# WX0_010_982DL_1.net
KiCad netlist of a schematic drawn in Altium Designer
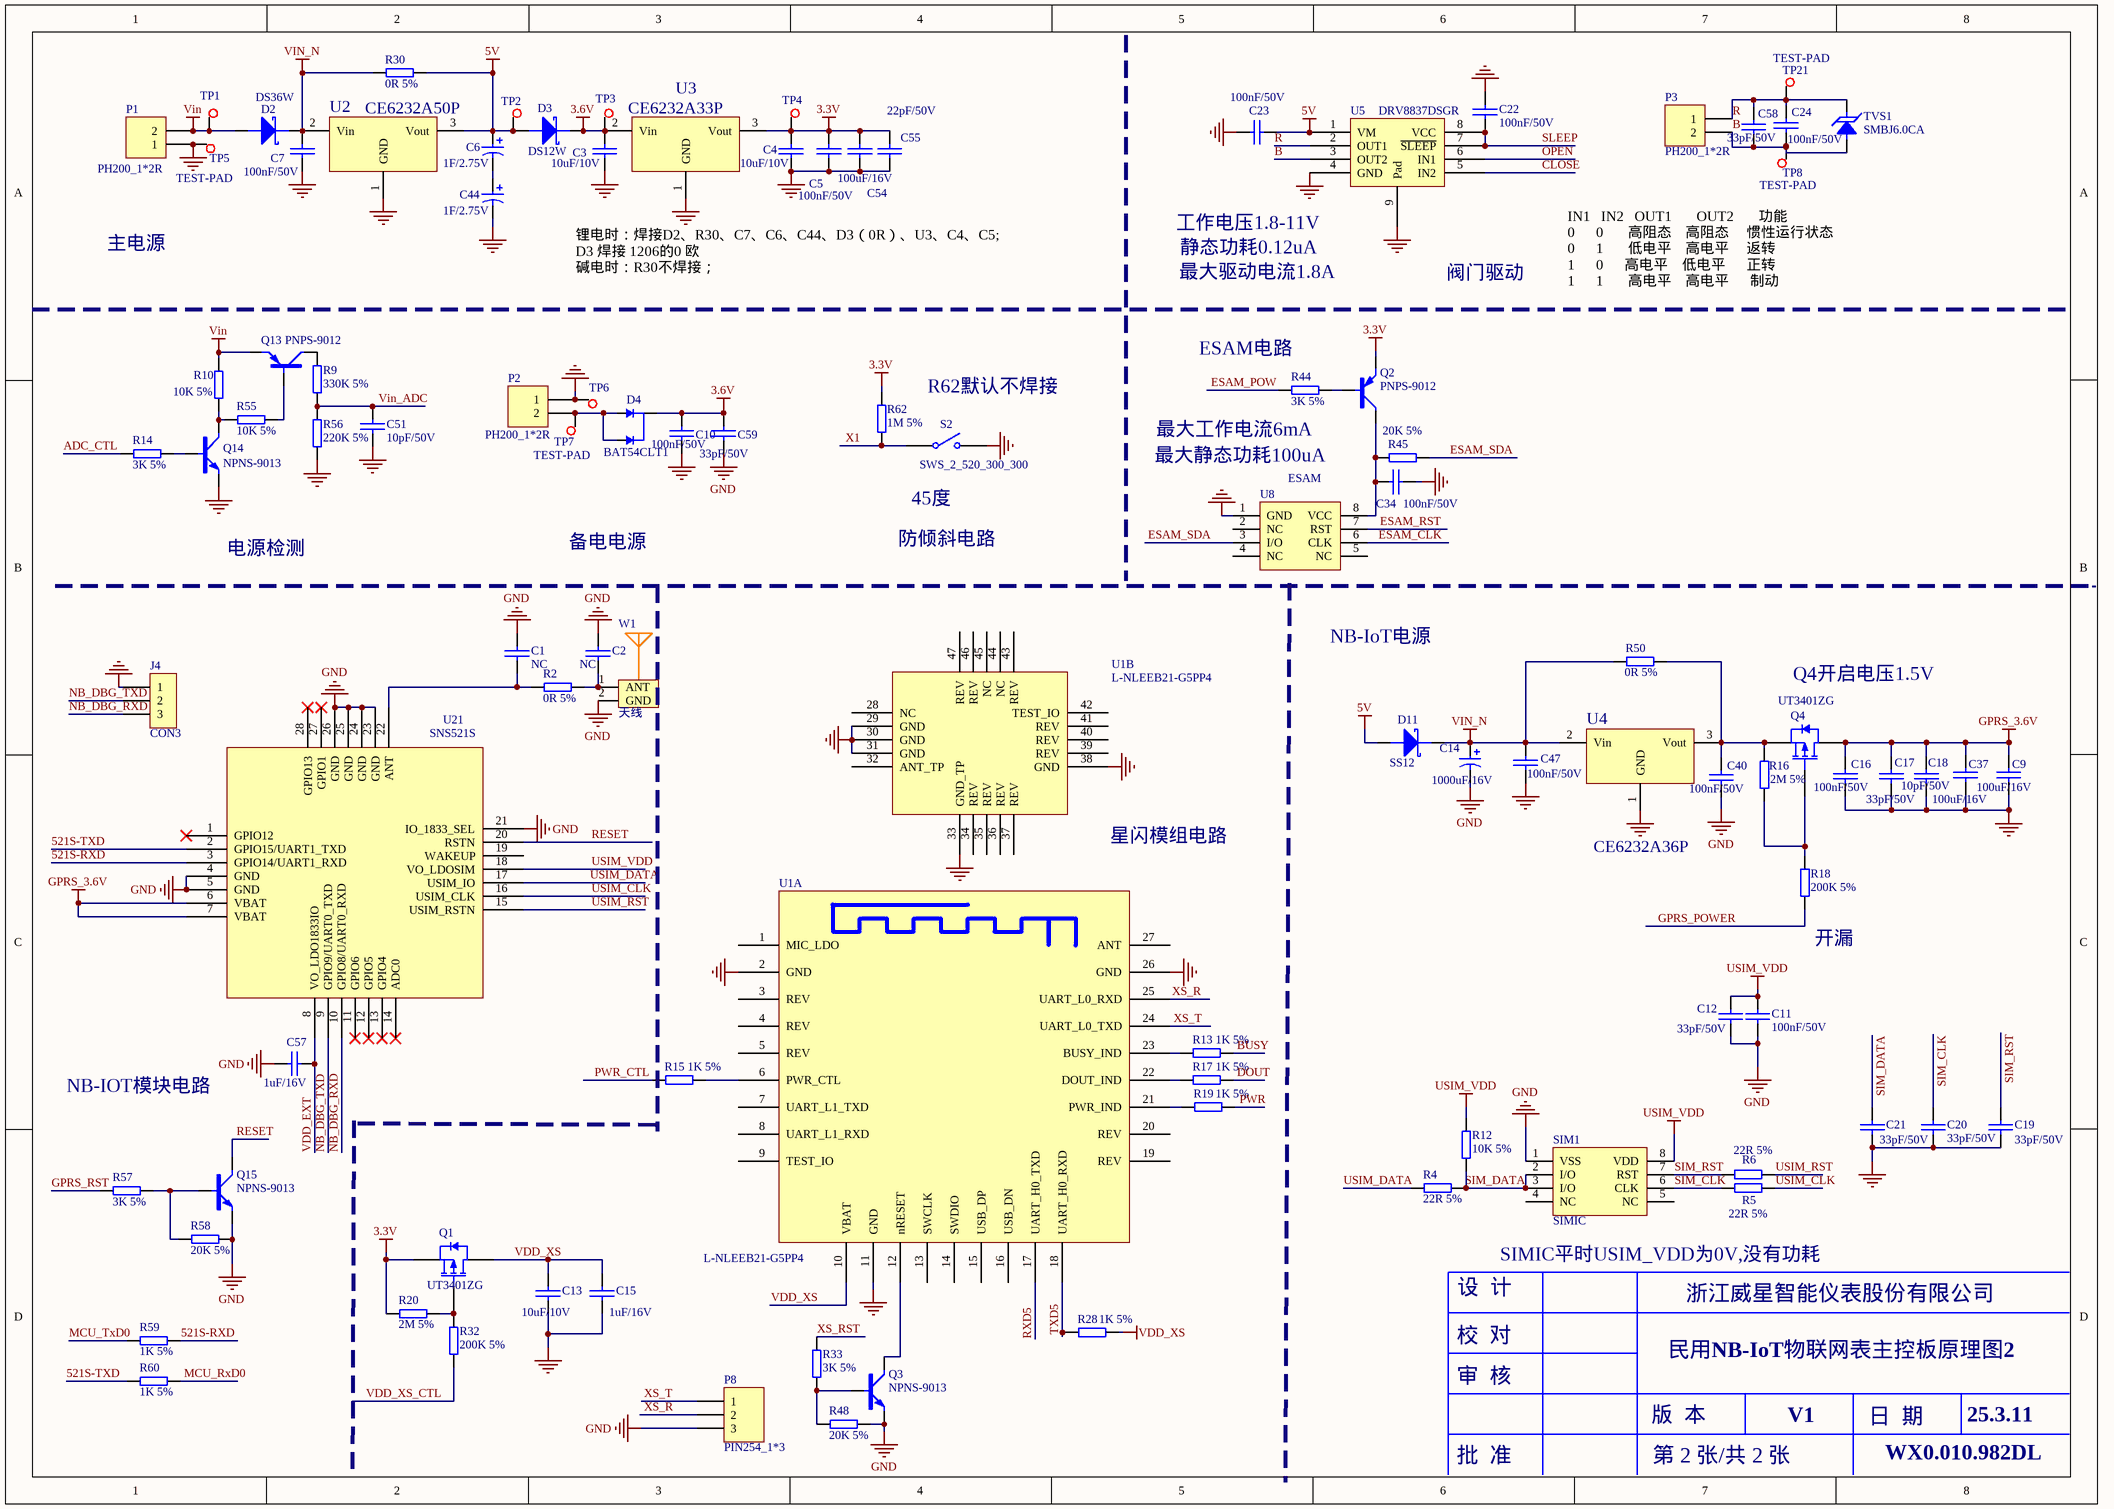
[diagram p0: WX0.010.982DL(1).SchDoc]

(export (version "E")
  (design (tool "Eeschema 10.0.6"))
  (components
    (comp (ref "C1")
      (value "NC")
      (footprint "CAP0603")
      (libsource (lib "Database_Libs2") (part "CC03JPO9_12P"))
    )
    (comp (ref "C2")
      (value "NC")
      (footprint "CAP0603")
      (libsource (lib "Database_Libs2") (part "CC03JPO9_12P"))
    )
    (comp (ref "C3")
      (value "10uF/10V")
      (footprint "CAP0603")
      (description "106pF,10 V,±10%,0603,村田,GRM188R61A106KE47D")
      (fields (field (name "PART NUMBER") "101020103-0026"))
      (libsource (lib "Database_Libs2") (part "CC03K5R6_10U"))
    )
    (comp (ref "C4")
      (value "10uF/10V")
      (footprint "CAP0603")
      (description "106pF,10 V,±10%,0603,村田,GRM188R61A106KE47D")
      (fields (field (name "PART NUMBER") "101020103-0026"))
      (libsource (lib "Database_Libs2") (part "CC03K5R6_10U"))
    )
    (comp (ref "C5")
      (value "100nF/50V")
      (footprint "CAP0603")
      (description "104pF,50 V,±10%,0603,国巨,CC0603KRX7R9BB104")
      (fields (field (name "PART NUMBER") "101020103-0021"))
      (libsource (lib "Database_Libs2") (part "CC03K7R9_100N"))
    )
    (comp (ref "C6")
      (value "1F/2.75V")
      (footprint "CAPPC_350_800_1600R")
      (description "1F,2.75 V,-20%~+20%,8mm*16mm,红宝石,2.7 DMC 1 M MY4 8X16")
      (fields (field (name "PART NUMBER") "1010202-0015"))
      (libsource (lib "Database_Libs2") (part "CALM3MRDMC_1F"))
    )
    (comp (ref "C7")
      (value "100nF/50V")
      (footprint "CAP0603")
      (description "104pF,50 V,±10%,0603,国巨,CC0603KRX7R9BB104")
      (fields (field (name "PART NUMBER") "101020103-0021"))
      (libsource (lib "Database_Libs2") (part "CC03K7R9_100N"))
    )
    (comp (ref "C9")
      (value "100uF/16V")
      (footprint "GRM31CR60J107ME39L")
      (libsource (lib "Database_Libs2") (part "CC06KPO7_106P"))
    )
    (comp (ref "C10")
      (value "100nF/50V")
      (footprint "CAP0603")
      (description "104pF,50 V,±10%,0603,国巨,CC0603KRX7R9BB104")
      (fields (field (name "PART NUMBER") "101020103-0021"))
      (libsource (lib "Database_Libs2") (part "CC03K7R9_100N"))
    )
    (comp (ref "C11")
      (value "100nF/50V")
      (footprint "CAP0603")
      (description "104pF,50 V,±10%,0603,国巨,CC0603KRX7R9BB104")
      (fields (field (name "PART NUMBER") "101020103-0021"))
      (libsource (lib "Database_Libs2") (part "CC03K7R9_100N"))
    )
    (comp (ref "C12")
      (value "33pF/50V")
      (footprint "CAP0603")
      (description "33pF,50 V,±10%,0603,国巨,CC0603KRNPO9BN33")
      (fields (field (name "PART NUMBER") "101020103-0027"))
      (libsource (lib "Database_Libs2") (part "CC03KPO9_33P"))
    )
    (comp (ref "C13")
      (value "10uF/10V")
      (footprint "CAP0603")
      (description "106pF,10 V,±10%,0603,村田,GRM188R61A106KE47D")
      (fields (field (name "PART NUMBER") "101020103-0026"))
      (libsource (lib "Database_Libs2") (part "CC03K5R6_10U"))
    )
    (comp (ref "C14")
      (value "1000uF/16V")
      (footprint "CAPPC_500_800_2000R")
      (description "1000UF,16V,±20%,贴片10*10.2MM,深圳市三炎科电子科技有限公司,16V1000UF")
      (fields (field (name "PART NUMBER") "1010203-0026"))
      (libsource (lib "Database_Libs2") (part "CAL7MRZLH_1000U_R"))
    )
    (comp (ref "C15")
      (value "1uF/16V")
      (footprint "CAP0603")
      (description "105pF,16 V,±10%,0603,国巨,CC0603KRX7R7BB105")
      (fields (field (name "PART NUMBER") "101020103-0003"))
      (libsource (lib "Database_Libs2") (part "CC03K7R7_1U"))
    )
    (comp (ref "C16")
      (value "100nF/50V")
      (footprint "CAP0603")
      (description "104pF,50 V,±10%,0603,国巨,CC0603KRX7R9BB104")
      (fields (field (name "PART NUMBER") "101020103-0021"))
      (libsource (lib "Database_Libs2") (part "CC03K7R9_100N"))
    )
    (comp (ref "C17")
      (value "33pF/50V")
      (footprint "CAP0603")
      (description "33pF,50 V,±10%,0603,国巨,CC0603KRNPO9BN33")
      (fields (field (name "PART NUMBER") "101020103-0027"))
      (libsource (lib "Database_Libs2") (part "CC03KPO9_33P"))
    )
    (comp (ref "C18")
      (value "10pF/50V")
      (footprint "CAP0603")
      (description "10pF,50 V,±5%,0603,X7R,国巨,CC0603JRNPO9BN100")
      (fields (field (name "PART NUMBER") "101020103-0014"))
      (libsource (lib "Database_Libs2") (part "CC03JPO9_10P"))
    )
    (comp (ref "C19")
      (value "33pF/50V")
      (footprint "CAP0603")
      (description "33pF,50 V,±10%,0603,国巨,CC0603KRNPO9BN33")
      (fields (field (name "PART NUMBER") "101020103-0027"))
      (libsource (lib "Database_Libs2") (part "CC03KPO9_33P"))
    )
    (comp (ref "C20")
      (value "33pF/50V")
      (footprint "CAP0603")
      (description "33pF,50 V,±10%,0603,国巨,CC0603KRNPO9BN33")
      (fields (field (name "PART NUMBER") "101020103-0027"))
      (libsource (lib "Database_Libs2") (part "CC03KPO9_33P"))
    )
    (comp (ref "C21")
      (value "33pF/50V")
      (footprint "CAP0603")
      (description "33pF,50 V,±10%,0603,国巨,CC0603KRNPO9BN33")
      (fields (field (name "PART NUMBER") "101020103-0027"))
      (libsource (lib "Database_Libs2") (part "CC03KPO9_33P"))
    )
    (comp (ref "C22")
      (value "100nF/50V")
      (footprint "CAP0603")
      (description "104pF,50 V,±10%,0603,国巨,CC0603KRX7R9BB104")
      (fields (field (name "PART NUMBER") "101020103-0021"))
      (libsource (lib "Database_Libs2") (part "CC03K7R9_100N"))
    )
    (comp (ref "C23")
      (value "100nF/50V")
      (footprint "CAP0603")
      (description "104pF,50 V,±10%,0603,国巨,CC0603KRX7R9BB104")
      (fields (field (name "PART NUMBER") "101020103-0021"))
      (libsource (lib "Database_Libs2") (part "CC03K7R9_100N"))
    )
    (comp (ref "C24")
      (value "100nF/50V")
      (footprint "CAP0603")
      (description "104pF,50 V,±10%,0603,国巨,CC0603KRX7R9BB104")
      (fields (field (name "PART NUMBER") "101020103-0021"))
      (libsource (lib "Database_Libs2") (part "CC03K7R9_100N"))
    )
    (comp (ref "C34")
      (value "100nF/50V")
      (footprint "CAP0603")
      (description "104pF,50 V,±10%,0603,国巨,CC0603KRX7R9BB104")
      (fields (field (name "PART NUMBER") "101020103-0021"))
      (libsource (lib "Database_Libs2") (part "CC03K7R9_100N"))
    )
    (comp (ref "C37")
      (value "100uF/16V")
      (footprint "GRM31CR60J107ME39L")
      (libsource (lib "Database_Libs2") (part "CC06KPO7_106P"))
    )
    (comp (ref "C40")
      (value "100nF/50V")
      (footprint "CAP0603")
      (description "104pF,50 V,±10%,0603,国巨,CC0603KRX7R9BB104")
      (fields (field (name "PART NUMBER") "101020103-0021"))
      (libsource (lib "Database_Libs2") (part "CC03K7R9_100N"))
    )
    (comp (ref "C44")
      (value "1F/2.75V")
      (footprint "CAPPC_350_800_1600R")
      (description "1F,2.75 V,-20%~+20%,8mm*16mm,红宝石,2.7 DMC 1 M MY4 8X16")
      (fields (field (name "PART NUMBER") "1010202-0015"))
      (libsource (lib "Database_Libs2") (part "CALM3MRDMC_1F"))
    )
    (comp (ref "C47")
      (value "100nF/50V")
      (footprint "CAP0603")
      (description "104pF,50 V,±10%,0603,国巨,CC0603KRX7R9BB104")
      (fields (field (name "PART NUMBER") "101020103-0021"))
      (libsource (lib "Database_Libs2") (part "CC03K7R9_100N"))
    )
    (comp (ref "C51")
      (value "10pF/50V")
      (footprint "CAP0603")
      (description "10pF,50 V,±5%,0603,X7R,国巨,CC0603JRNPO9BN100")
      (fields (field (name "PART NUMBER") "101020103-0014"))
      (libsource (lib "Database_Libs2") (part "CC03JPO9_10P"))
    )
    (comp (ref "C54")
      (value "100uF/16V")
      (footprint "GRM31CR60J107ME39L")
      (description "100u,16 V,±10%,1206,国巨,CC1206KRNPO7BN106P")
      (libsource (lib "Database_Libs2") (part "CC06KPO7_106P"))
    )
    (comp (ref "C55")
      (value "22pF/50V")
      (footprint "CAP0603")
      (description "22pF,50 V,±5%,0603,国巨,CC0603JRNPO9BN22")
      (fields (field (name "PART NUMBER") "101020103-0009"))
      (libsource (lib "Database_Libs2") (part "CC03JPO9_22P"))
    )
    (comp (ref "C57")
      (value "1uF/16V")
      (footprint "CAP0603")
      (description "105pF,16 V,±10%,0603,国巨,CC0603KRX7R7BB105")
      (fields (field (name "PART NUMBER") "101020103-0003"))
      (libsource (lib "Database_Libs1") (part "CC03K7R7_1U"))
    )
    (comp (ref "C58")
      (value "33pF/50V")
      (footprint "CAP0603")
      (description "104pF,50 V,±10%,0603,国巨,CC0603KRX7R9BB104")
      (fields (field (name "PART NUMBER") "101020103-0021"))
      (libsource (lib "Database_Libs2") (part "CC03K7R9_100N"))
    )
    (comp (ref "C59")
      (value "33pF/50V")
      (footprint "CAP0603")
      (description "104pF,50 V,±10%,0603,国巨,CC0603KRX7R9BB104")
      (fields (field (name "PART NUMBER") "101020103-0021"))
      (libsource (lib "Database_Libs2") (part "CC03K7R9_100N"))
    )
    (comp (ref "D2")
      (value "DS36W")
      (footprint "SOD-123FL")
      (description "DS36W,SOD123-FL,3 A,42 V,60 V,浙江领晨科技有限公司,DS36W")
      (fields (field (name "PART NUMBER") "101040101-0055"))
      (libsource (lib "Database_Libs2") (part "02_DS12W"))
    )
    (comp (ref "D3")
      (value "DS12W")
      (footprint "SOD-123FL")
      (description "DS12W,SOD-123FL,1 A,0.55 V,20 V,领晨科技,DS12W")
      (fields (field (name "PART NUMBER") "101040101-0048"))
      (libsource (lib "Database_Libs2") (part "02_DS12W"))
    )
    (comp (ref "D4")
      (value "BAT54CLT1")
      (footprint "SOT-23")
      (description "BAT54CLT1，SOT23-3,SOT23-3,0.2 A,0.8 V,30 V,安森美,BAT54CLT1")
      (fields (field (name "PART NUMBER") "101040101-0038"))
      (libsource (lib "Database_Libs2") (part "02_BAT54CLT1"))
    )
    (comp (ref "D11")
      (value "SS12")
      (footprint "DO-214AC")
      (description "SS12,DO-214AC,1 A,0.55 V,20 V,昶鑫,SS12")
      (fields (field (name "PART NUMBER") "101040101-0009"))
      (libsource (lib "Database_Libs2") (part "02_SS12"))
    )
    (comp (ref "J4")
      (value "CON3")
      (footprint "PIN254_1*3*WXHJ")
      (description "Connector")
      (libsource (lib "Miscellaneous Devices") (part "CON3"))
    )
    (comp (ref "P1")
      (value "PH200_1*2R")
      (description "2.0-2AW,直插弯座，2PIN，脚间距2mm，带防翘起,公头,单排,2.0-2AW;直插弯座，2PIN,脚间距2mm，带防翘起")
      (fields (field (name "PART NUMBER") "1010902-0105"))
      (libsource (lib "") (part "PH200_1*2R_1"))
    )
    (comp (ref "P2")
      (value "PH200_1*2R")
      (description "2.0-2AW,直插弯座，2PIN，脚间距2mm，带防翘起,公头,单排,2.0-2AW;直插弯座，2PIN,脚间距2mm，带防翘起")
      (fields (field (name "PART NUMBER") "1010902-0105"))
      (libsource (lib "Database_Libs2") (part "PH200_1*2R"))
    )
    (comp (ref "P3")
      (value "PH200_1*2R")
      (footprint "PH200_1*2R")
      (description "2.0-2AW,直插弯座，2PIN，脚间距2mm，带防翘起,公头,单排,2.0-2AW;直插弯座，2PIN,脚间距2mm，带防翘起")
      (fields (field (name "PART NUMBER") "1010902-0105"))
      (libsource (lib "Database_Libs2") (part "PH200_1*2R"))
    )
    (comp (ref "P8")
      (value "PIN254_1*3")
      (footprint "PIN254_1*3*WXHJ")
      (libsource (lib "Connect_WX") (part "PIN254_1*3"))
    )
    (comp (ref "Q1")
      (value "UT3401ZG")
      (footprint "SOT-23")
      (description "UT3401ZG,P-MOS,SOT-23,UTC,UT3401ZG")
      (fields (field (name "PART NUMBER") "101040201-0013"))
      (libsource (lib "Database_Libs2") (part "03_P-UT3401ZG"))
    )
    (comp (ref "Q2")
      (value "PNPS-9012")
      (footprint "SOT-23")
      (description "9012,PNP,SOT-23,JCET;长电,S9012")
      (fields (field (name "PART NUMBER") "101040201-0001"))
      (libsource (lib "Database_Libs2") (part "03_PNPS-9012"))
    )
    (comp (ref "Q3")
      (value "NPNS-9013")
      (footprint "SOT-23")
      (description "9013,NPN,SOT-23,长电,S9013")
      (fields (field (name "PART NUMBER") "101040201-0002"))
      (libsource (lib "Database_Libs2") (part "03_NPNS-9013"))
    )
    (comp (ref "Q4")
      (value "UT3401ZG")
      (footprint "SOT-23")
      (description "UT3401ZG,P-MOS,SOT-23,UTC,UT3401ZG")
      (fields (field (name "PART NUMBER") "101040201-0013"))
      (libsource (lib "Database_Libs2") (part "03_P-UT3401ZG"))
    )
    (comp (ref "Q13")
      (value "PNPS-9012")
      (footprint "SOT-23")
      (description "9012,PNP,SOT-23,JCET;长电,S9012")
      (fields (field (name "PART NUMBER") "101040201-0001"))
      (libsource (lib "Database_Libs2") (part "03_PNPS-9012"))
    )
    (comp (ref "Q14")
      (value "NPNS-9013")
      (footprint "SOT-23")
      (description "9013,NPN,SOT-23,长电,S9013")
      (fields (field (name "PART NUMBER") "101040201-0002"))
      (libsource (lib "Database_Libs2") (part "03_NPNS-9013"))
    )
    (comp (ref "Q15")
      (value "NPNS-9013")
      (footprint "SOT-23")
      (description "9013,NPN,SOT-23,长电,S9013")
      (fields (field (name "PART NUMBER") "101040201-0002"))
      (libsource (lib "Database_Libs2") (part "03_NPNS-9013"))
    )
    (comp (ref "R2")
      (value "0R 5%")
      (footprint "RES0603")
      (description "国巨,±5%,0603,,155 ℃,-55 ℃,RC0603J2-070RL,无铅,200 ppm/℃,1/10W,,0R")
      (fields (field (name "PART NUMBER") "101010103-0001"))
      (libsource (lib "Database_Libs2") (part "RC03J_0R"))
    )
    (comp (ref "R4")
      (value "22R 5%")
      (footprint "RES0603")
      (description "国巨,±5%,0603,,155 ℃,-55 ℃,RC0603JR-0722RL,无铅,200 ppm/℃,1/10W,,22欧")
      (fields (field (name "PART NUMBER") "101010103-0009"))
      (libsource (lib "Database_Libs2") (part "RC03J_22R"))
    )
    (comp (ref "R5")
      (value "22R 5%")
      (footprint "RES0603")
      (description "国巨,±5%,0603,,155 ℃,-55 ℃,RC0603JR-0722RL,无铅,200 ppm/℃,1/10W,,22欧")
      (fields (field (name "PART NUMBER") "101010103-0009"))
      (libsource (lib "Database_Libs2") (part "RC03J_22R"))
    )
    (comp (ref "R6")
      (value "22R 5%")
      (footprint "RES0603")
      (description "国巨,±5%,0603,,155 ℃,-55 ℃,RC0603JR-0722RL,无铅,200 ppm/℃,1/10W,,22欧")
      (fields (field (name "PART NUMBER") "101010103-0009"))
      (libsource (lib "Database_Libs2") (part "RC03J_22R"))
    )
    (comp (ref "R9")
      (value "330K 5%")
      (footprint "RES0603")
      (description "330K,±5%,1/10W,0603,国巨,RC0603JR-07330KL")
      (fields (field (name "PART NUMBER") "101010103-0066"))
      (libsource (lib "Database_Libs2") (part "RC03J_330K"))
    )
    (comp (ref "R10")
      (value "10K 5%")
      (footprint "RES0603")
      (description "国巨,±5%,0603,,155 ℃,-55 ℃,RC0603JR-0710KL,无铅,200 ppm/℃,1/10W,,10K")
      (fields (field (name "PART NUMBER") "101010103-0003"))
      (libsource (lib "Database_Libs2") (part "RC03J_10K"))
    )
    (comp (ref "R12")
      (value "10K 5%")
      (footprint "RES0603")
      (description "国巨,±5%,0603,,155 ℃,-55 ℃,RC0603JR-0722RL,无铅,200 ppm/℃,1/10W,,22欧")
      (fields (field (name "PART NUMBER") "101010103-0009"))
      (libsource (lib "Database_Libs2") (part "RC03J_22R"))
    )
    (comp (ref "R13")
      (value "1K 5%")
      (footprint "RES0603")
      (description "1K,±5%,1/10W,0603,国巨,RC0603JR-071KL")
      (fields (field (name "PART NUMBER") "101010103-0008"))
      (libsource (lib "Database_Libs2") (part "RC03J_1K"))
    )
    (comp (ref "R14")
      (value "3K 5%")
      (footprint "RES0603")
      (description "国巨,±5%,0603,,155 ℃,-55 ℃,RC0603JR-073KL,无铅,100 ppm/℃,1/10W,,3K")
      (fields (field (name "PART NUMBER") "101010103-0006"))
      (libsource (lib "Database_Libs2") (part "RC03J_3K"))
    )
    (comp (ref "R15")
      (value "1K 5%")
      (footprint "RES0603")
      (description "1K,±5%,1/10W,0603,国巨,RC0603JR-071KL")
      (fields (field (name "PART NUMBER") "101010103-0008"))
      (libsource (lib "Database_Libs2") (part "RC03J_1K"))
    )
    (comp (ref "R16")
      (value "2M 5%")
      (footprint "RES0603")
      (description "国巨,±5%,0603,,155 ℃,-55 ℃,RC0603JR-072ML,含铅,100 ppm/℃,1/10W,,2M")
      (fields (field (name "PART NUMBER") "101010103-0025"))
      (libsource (lib "Database_Libs2") (part "RC03J_2M"))
    )
    (comp (ref "R17")
      (value "1K 5%")
      (footprint "RES0603")
      (description "1K,±5%,1/10W,0603,国巨,RC0603JR-071KL")
      (fields (field (name "PART NUMBER") "101010103-0008"))
      (libsource (lib "Database_Libs2") (part "RC03J_1K"))
    )
    (comp (ref "R18")
      (value "200K 5%")
      (footprint "RES0603")
      (description "200K,±5%,1/10W,0603,国巨,RC0603JR-07200KL")
      (fields (field (name "PART NUMBER") "101010103-0034"))
      (libsource (lib "Database_Libs2") (part "RC03J_200K"))
    )
    (comp (ref "R19")
      (value "1K 5%")
      (footprint "RES0603")
      (description "1K,±5%,1/10W,0603,国巨,RC0603JR-071KL")
      (fields (field (name "PART NUMBER") "101010103-0008"))
      (libsource (lib "Database_Libs2") (part "RC03J_1K"))
    )
    (comp (ref "R20")
      (value "2M 5%")
      (footprint "RES0603")
      (description "10K±5%,1/10W,0603")
      (fields (field (name "PART NUMBER") "101010103-0003"))
      (libsource (lib "Database_Libs1") (part "RC03JF_10K"))
    )
    (comp (ref "R28")
      (value "1K 5%")
      (footprint "RES0603")
      (description "1K,±5%,1/10W,0603,国巨,RC0603JR-071KL")
      (fields (field (name "PART NUMBER") "101010103-0008"))
      (libsource (lib "Database_Libs2") (part "RC03J_1K"))
    )
    (comp (ref "R30")
      (value "0R 5%")
      (footprint "RES1206")
      (description "0Ω,±5%,1/4W,1206,国巨,RC1206JR-070RL")
      (fields (field (name "PART NUMBER") "101010101-0013"))
      (libsource (lib "Database_Libs2") (part "RC06J_0R"))
    )
    (comp (ref "R32")
      (value "200K 5%")
      (footprint "RES0603")
      (description "10K±5%,1/10W,0603")
      (fields (field (name "PART NUMBER") "101010103-0003"))
      (libsource (lib "Database_Libs1") (part "RC03JF_10K"))
    )
    (comp (ref "R33")
      (value "3K 5%")
      (footprint "RES0603")
      (description "国巨,±5%,0603,,155 ℃,-55 ℃,RC0603JR-073KL,无铅,100 ppm/℃,1/10W,,3K")
      (fields (field (name "PART NUMBER") "101010103-0006"))
      (libsource (lib "Database_Libs2") (part "RC03J_3K"))
    )
    (comp (ref "R44")
      (value "3K 5%")
      (footprint "RES0603")
      (description "国巨,±5%,0603,,155 ℃,-55 ℃,RC0603JR-0710KL,无铅,200 ppm/℃,1/10W,,10K")
      (fields (field (name "PART NUMBER") "101010103-0003"))
      (libsource (lib "Database_Libs2") (part "RC03J_10K"))
    )
    (comp (ref "R45")
      (value "20K 5%")
      (footprint "RES0603")
      (description "国巨,±5%,0603,,155 ℃,-55 ℃,RC0603JR-0720KL,无铅,200 ppm/℃,1/10W,,20K")
      (fields (field (name "PART NUMBER") "101010103-0004"))
      (libsource (lib "Database_Libs2") (part "RC03J_20K"))
    )
    (comp (ref "R48")
      (value "20K 5%")
      (footprint "RES0603")
      (description "国巨,±5%,0603,,155 ℃,-55 ℃,RC0603JR-0720KL,无铅,200 ppm/℃,1/10W,,20K")
      (fields (field (name "PART NUMBER") "101010103-0004"))
      (libsource (lib "Database_Libs2") (part "RC03J_20K"))
    )
    (comp (ref "R50")
      (value "0R 5%")
      (footprint "RES1206")
      (description "0Ω,±5%,1/4W,1206,国巨,RC1206JR-070RL")
      (fields (field (name "PART NUMBER") "101010101-0013"))
      (libsource (lib "Database_Libs2") (part "RC06J_0R"))
    )
    (comp (ref "R55")
      (value "10K 5%")
      (footprint "RES0603")
      (description "国巨,±5%,0603,,155 ℃,-55 ℃,RC0603JR-0710KL,无铅,200 ppm/℃,1/10W,,10K")
      (fields (field (name "PART NUMBER") "101010103-0003"))
      (libsource (lib "Database_Libs2") (part "RC03J_10K"))
    )
    (comp (ref "R56")
      (value "220K 5%")
      (footprint "RES0603")
      (description "220K,±5%,1/10W,0603,国巨,RC0603JR-07220KL")
      (fields (field (name "PART NUMBER") "101010103-0044"))
      (libsource (lib "Database_Libs2") (part "RC03J_220K"))
    )
    (comp (ref "R57")
      (value "3K 5%")
      (footprint "RES0603")
      (description "国巨,±5%,0603,,155 ℃,-55 ℃,RC0603JR-073KL,无铅,100 ppm/℃,1/10W,,3K")
      (fields (field (name "PART NUMBER") "101010103-0006"))
      (libsource (lib "Database_Libs2") (part "RC03J_3K"))
    )
    (comp (ref "R58")
      (value "20K 5%")
      (footprint "RES0603")
      (description "国巨,±5%,0603,,155 ℃,-55 ℃,RC0603JR-0720KL,无铅,200 ppm/℃,1/10W,,20K")
      (fields (field (name "PART NUMBER") "101010103-0004"))
      (libsource (lib "Database_Libs2") (part "RC03J_20K"))
    )
    (comp (ref "R59")
      (value "1K 5%")
      (footprint "RES0603")
      (description "4.7K±5%,1/10W,0603")
      (fields (field (name "PART NUMBER") "101010103-0042"))
      (libsource (lib "Database_Libs2") (part "RC03J_4.7K"))
    )
    (comp (ref "R60")
      (value "1K 5%")
      (footprint "RES0603")
      (description "1K,±5%,1/10W,0603,国巨,RC0603JR-071KL")
      (fields (field (name "PART NUMBER") "101010103-0008"))
      (libsource (lib "Database_Libs2") (part "RC03J_1K"))
    )
    (comp (ref "R62")
      (value "1M 5%")
      (footprint "RES0603")
      (description "国巨,±5%,0603,,155 ℃,-55 ℃,RC0603JR-071ML,无铅,200 ppm/℃,1/10W,,1M")
      (fields (field (name "PART NUMBER") "101010103-0002"))
      (libsource (lib "Database_Libs2") (part "RC03J_1M"))
    )
    (comp (ref "S2")
      (value "SWS_2_520_300_300")
      (footprint "SWS_2_520_300")
      (description "CSX-SEN-645B,垂直45°开关转换,3*5.2mm,360°任意方位倾斜检测,深圳市成晟科技有限公司")
      (fields (field (name "PART NUMBER") "1011001-0051"))
      (libsource (lib "Database_Libs2") (part "07_SWS_2_520_300_300"))
    )
    (comp (ref "SIM1")
      (value "SIMIC")
      (footprint "SIMIC")
      (description "SIMIC虚拟器件")
      (fields (field (name "PART NUMBER") "AD_XN_SIMIC_01"))
      (libsource (lib "Database_Libs2") (part "05_SIMIC"))
    )
    (comp (ref "TP1")
      (value "TEST-PAD")
      (footprint "TEST-PAD")
      (description "单面焊盘测试点")
      (fields (field (name "PART NUMBER") "AD_WXHJ_TEST-PAD_01"))
      (libsource (lib "Database_Libs2") (part "TEST-PAD"))
    )
    (comp (ref "TP2")
      (value "TEST-PAD")
      (footprint "TEST-PAD")
      (description "单面焊盘测试点")
      (fields (field (name "PART NUMBER") "AD_WXHJ_TEST-PAD_01"))
      (libsource (lib "Database_Libs2") (part "TEST-PAD"))
    )
    (comp (ref "TP3")
      (value "TEST-PAD")
      (footprint "TEST-PAD")
      (description "单面焊盘测试点")
      (fields (field (name "PART NUMBER") "AD_WXHJ_TEST-PAD_01"))
      (libsource (lib "Database_Libs2") (part "TEST-PAD"))
    )
    (comp (ref "TP4")
      (value "TEST-PAD")
      (footprint "TEST-PAD")
      (description "单面焊盘测试点")
      (fields (field (name "PART NUMBER") "AD_WXHJ_TEST-PAD_01"))
      (libsource (lib "Database_Libs2") (part "TEST-PAD"))
    )
    (comp (ref "TP5")
      (value "TEST-PAD")
      (footprint "TEST-PAD")
      (description "单面焊盘测试点")
      (fields (field (name "PART NUMBER") "AD_WXHJ_TEST-PAD_01"))
      (libsource (lib "Database_Libs2") (part "TEST-PAD"))
    )
    (comp (ref "TP6")
      (value "TEST-PAD")
      (footprint "TEST-PAD")
      (description "单面焊盘测试点")
      (fields (field (name "PART NUMBER") "AD_WXHJ_TEST-PAD_01"))
      (libsource (lib "Database_Libs2") (part "TEST-PAD"))
    )
    (comp (ref "TP7")
      (value "TEST-PAD")
      (footprint "TEST-PAD")
      (description "单面焊盘测试点")
      (fields (field (name "PART NUMBER") "AD_WXHJ_TEST-PAD_01"))
      (libsource (lib "Database_Libs2") (part "TEST-PAD"))
    )
    (comp (ref "TP8")
      (value "TEST-PAD")
      (footprint "TEST-PAD")
      (description "单面焊盘测试点")
      (fields (field (name "PART NUMBER") "AD_WXHJ_TEST-PAD_01"))
      (libsource (lib "Database_Libs2") (part "TEST-PAD"))
    )
    (comp (ref "TP21")
      (value "TEST-PAD")
      (footprint "TEST-PAD")
      (description "单面焊盘测试点")
      (fields (field (name "PART NUMBER") "AD_WXHJ_TEST-PAD_01"))
      (libsource (lib "Database_Libs2") (part "TEST-PAD"))
    )
    (comp (ref "TVS1")
      (value "SMBJ6.0CA")
      (footprint "DO-214AA")
      (description "SMBJ6.0CA,DO-214AA,10.3 V,6.0 V,600 W,58.3 A,800 uA,上海君耀电子有限公司,SMBJ6.0CA")
      (fields (field (name "PART NUMBER") "101040101-0024"))
      (libsource (lib "Database_Libs2") (part "05_SMBJ6.0CA"))
    )
    (comp (ref "U1")
      (value "L-NLEEB21-G5PP4")
      (footprint "L-NLEEB21-G5BP4")
      (libsource (lib "L-NLEEB21-G5BP4_V03") (part "L-NLEEB21-G5BP4"))
    )
    (comp (ref "U2")
      (value "CE6232A50P")
      (footprint "SOT-89")
      (fields (field (name "PART NUMBER") "1010503-0013"))
      (libsource (lib "Database_Libs2") (part "02_S-1206B50-U3"))
    )
    (comp (ref "U3")
      (value "CE6232A33P")
      (footprint "SOT-89")
      (fields (field (name "PART NUMBER") "1010503-0002"))
      (libsource (lib "Database_Libs2") (part "02_S-1206B33-U3T1G"))
    )
    (comp (ref "U4")
      (value "CE6232A36P")
      (footprint "SOT-89")
      (description "CE6232A36P,CE6232A36P,SOT89-3,8 V,1.8 V,0.11 V,3.6 V,600mA,0.8 uA,南京芯力微电子有限公司")
      (fields (field (name "PART NUMBER") "1010503-0031"))
      (libsource (lib "Database_Libs2") (part "02_CE6232A36P"))
    )
    (comp (ref "U5")
      (value "DRV8837DSGR")
      (footprint "S-PWSON-N8")
      (description "DRV8837DSGR,S-PWSON-N8,TI,DRV8837DSGR")
      (fields (field (name "PART NUMBER") "101050101-0060"))
      (libsource (lib "Database_Libs2") (part "07_DRV8837DSGR"))
    )
    (comp (ref "U8")
      (value "ESAM")
      (footprint "SOP-8")
      (description "ESAM虚拟器件")
      (fields (field (name "PART NUMBER") "AD_XN_ESAM_01"))
      (libsource (lib "Database_Libs2") (part "04_ESAM"))
    )
    (comp (ref "U21") (value "SNS521S") (libsource (lib "Schlib1") (part "OUT")))
    (comp (ref "W1")
      (value "天线")
      (footprint "ANT-IPEX_1")
      (description "UB06000058A,3*3.1*1.25mm,公头,单排,IPEX一代板端")
      (fields (field (name "PART NUMBER") "1010902-0145"))
      (libsource (lib "Database_Libs2") (part "天线"))
    )
  )
  (nets
    (net (code "1") (name "/521S-RXD") (class "Default")
      (node (ref "R59") (pin "1") (pinfunction "1_1") (pintype "passive"))
      (node (ref "U21") (pin "3") (pinfunction "GPIO14/UART1_RXD_3") (pintype "passive"))
    )
    (net (code "2") (name "/521S-TXD") (class "Default")
      (node (ref "R60") (pin "2") (pinfunction "2_2") (pintype "passive"))
      (node (ref "U21") (pin "2") (pinfunction "GPIO15/UART1_TXD_2") (pintype "passive"))
    )
    (net (code "3") (name "/ADC_CTL") (class "Default")
      (node (ref "R14") (pin "1") (pinfunction "1_1") (pintype "passive"))
    )
    (net (code "4") (name "/B") (class "Default")
      (node (ref "C24") (pin "2") (pinfunction "2_2") (pintype "passive"))
      (node (ref "C58") (pin "2") (pinfunction "2_2") (pintype "passive"))
      (node (ref "P3") (pin "2") (pinfunction "2_2") (pintype "passive"))
      (node (ref "TP8") (pin "1") (pinfunction "1_1") (pintype "passive"))
      (node (ref "TVS1") (pin "1") (pinfunction "1_1") (pintype "passive"))
      (node (ref "U5") (pin "3") (pinfunction "OUT2_3") (pintype "passive"))
    )
    (net (code "5") (name "/BUSY") (class "Default")
      (node (ref "R13") (pin "1") (pinfunction "1_1") (pintype "passive"))
    )
    (net (code "6") (name "/CLOSE") (class "Default")
      (node (ref "U5") (pin "5") (pinfunction "IN2_5") (pintype "passive"))
    )
    (net (code "7") (name "/DOUT") (class "Default")
      (node (ref "R17") (pin "1") (pinfunction "1_1") (pintype "passive"))
    )
    (net (code "8") (name "/ESAM_CLK") (class "Default")
      (node (ref "U8") (pin "6") (pinfunction "CLK_6") (pintype "passive"))
    )
    (net (code "9") (name "/ESAM_POW") (class "Default")
      (node (ref "R44") (pin "1") (pinfunction "1_1") (pintype "passive"))
    )
    (net (code "10") (name "/ESAM_RST") (class "Default")
      (node (ref "U8") (pin "7") (pinfunction "RST_7") (pintype "passive"))
    )
    (net (code "11") (name "/ESAM_SDA") (class "Default")
      (node (ref "R45") (pin "2") (pinfunction "2_2") (pintype "passive"))
      (node (ref "U8") (pin "3") (pinfunction "I/O_3") (pintype "passive"))
    )
    (net (code "12") (name "/GPRS_POWER") (class "Default")
      (node (ref "R18") (pin "1") (pinfunction "1_1") (pintype "passive"))
    )
    (net (code "13") (name "/GPRS_RST") (class "Default")
      (node (ref "R57") (pin "1") (pinfunction "1_1") (pintype "passive"))
    )
    (net (code "14") (name "/MCU_RxD0") (class "Default")
      (node (ref "R60") (pin "1") (pinfunction "1_1") (pintype "passive"))
    )
    (net (code "15") (name "/MCU_TxD0") (class "Default")
      (node (ref "R59") (pin "2") (pinfunction "2_2") (pintype "passive"))
    )
    (net (code "16") (name "/NB_DBG_RXD") (class "Default")
      (node (ref "J4") (pin "3") (pinfunction "3_3") (pintype "passive"))
      (node (ref "U21") (pin "10") (pinfunction "GPIO8/UART0_RXD_10") (pintype "passive"))
    )
    (net (code "17") (name "/NB_DBG_TXD") (class "Default")
      (node (ref "J4") (pin "2") (pinfunction "2_2") (pintype "passive"))
      (node (ref "U21") (pin "9") (pinfunction "GPIO9/UART0_TXD_9") (pintype "passive"))
    )
    (net (code "18") (name "/OPEN") (class "Default")
      (node (ref "U5") (pin "6") (pinfunction "IN1_6") (pintype "passive"))
    )
    (net (code "19") (name "/PWR") (class "Default")
      (node (ref "R19") (pin "1") (pinfunction "1_1") (pintype "passive"))
    )
    (net (code "20") (name "/PWR_CTL") (class "Default")
      (node (ref "R15") (pin "2") (pinfunction "2_2") (pintype "passive"))
    )
    (net (code "21") (name "/R") (class "Default")
      (node (ref "C24") (pin "1") (pinfunction "1_1") (pintype "passive"))
      (node (ref "C58") (pin "1") (pinfunction "1_1") (pintype "passive"))
      (node (ref "P3") (pin "1") (pinfunction "1_1") (pintype "passive"))
      (node (ref "TP21") (pin "1") (pinfunction "1_1") (pintype "passive"))
      (node (ref "TVS1") (pin "2") (pinfunction "2_2") (pintype "passive"))
      (node (ref "U5") (pin "2") (pinfunction "OUT1_2") (pintype "passive"))
    )
    (net (code "22") (name "/RESET") (class "Default")
      (node (ref "Q15") (pin "3") (pinfunction "C_3") (pintype "passive"))
      (node (ref "U21") (pin "20") (pinfunction "RSTN_20") (pintype "passive"))
    )
    (net (code "23") (name "/RXD5") (class "Default")
      (node (ref "U1") (pin "17") (pinfunction "UART_H0_TXD_17") (pintype "passive"))
    )
    (net (code "24") (name "/SIM_CLK") (class "Default")
      (node (ref "C20") (pin "1") (pinfunction "1_1") (pintype "passive"))
      (node (ref "R5") (pin "1") (pinfunction "1_1") (pintype "passive"))
      (node (ref "SIM1") (pin "6") (pinfunction "CLK_6") (pintype "passive"))
    )
    (net (code "25") (name "/SIM_DATA") (class "Default")
      (node (ref "C21") (pin "1") (pinfunction "1_1") (pintype "passive"))
      (node (ref "R12") (pin "1") (pinfunction "1_1") (pintype "passive"))
      (node (ref "R4") (pin "2") (pinfunction "2_2") (pintype "passive"))
      (node (ref "SIM1") (pin "2") (pinfunction "I/O_2") (pintype "passive"))
      (node (ref "SIM1") (pin "3") (pinfunction "I/O_3") (pintype "passive"))
    )
    (net (code "26") (name "/SIM_RST") (class "Default")
      (node (ref "C19") (pin "1") (pinfunction "1_1") (pintype "passive"))
      (node (ref "R6") (pin "1") (pinfunction "1_1") (pintype "passive"))
      (node (ref "SIM1") (pin "7") (pinfunction "RST_7") (pintype "passive"))
    )
    (net (code "27") (name "/SLEEP") (class "Default")
      (node (ref "C22") (pin "2") (pinfunction "2_2") (pintype "passive"))
      (node (ref "U5") (pin "7") (pinfunction "~{SLEEP}_7") (pintype "passive"))
      (node (ref "U5") (pin "8") (pinfunction "VCC_8") (pintype "passive"))
    )
    (net (code "28") (name "/TXD5") (class "Default")
      (node (ref "R28") (pin "2") (pinfunction "2_2") (pintype "passive"))
      (node (ref "U1") (pin "18") (pinfunction "UART_H0_RXD_18") (pintype "passive"))
    )
    (net (code "29") (name "/USIM_CLK") (class "Default")
      (node (ref "R5") (pin "2") (pinfunction "2_2") (pintype "passive"))
      (node (ref "U21") (pin "16") (pinfunction "USIM_CLK_16") (pintype "passive"))
    )
    (net (code "30") (name "/USIM_DATA") (class "Default")
      (node (ref "R4") (pin "1") (pinfunction "1_1") (pintype "passive"))
      (node (ref "U21") (pin "17") (pinfunction "USIM_IO_17") (pintype "passive"))
    )
    (net (code "31") (name "/USIM_RST") (class "Default")
      (node (ref "R6") (pin "2") (pinfunction "2_2") (pintype "passive"))
      (node (ref "U21") (pin "15") (pinfunction "USIM_RSTN_15") (pintype "passive"))
    )
    (net (code "32") (name "/VDD_EXT") (class "Default")
      (node (ref "C57") (pin "1") (pinfunction "1_1") (pintype "passive"))
      (node (ref "U21") (pin "8") (pinfunction "VO_LDO1833IO_8") (pintype "passive"))
    )
    (net (code "33") (name "/VDD_XS_CTL") (class "Default")
      (node (ref "R32") (pin "1") (pinfunction "1_1") (pintype "passive"))
    )
    (net (code "34") (name "/Vin_ADC") (class "Default")
      (node (ref "C51") (pin "2") (pinfunction "2_2") (pintype "passive"))
      (node (ref "R56") (pin "1") (pinfunction "1_1") (pintype "passive"))
      (node (ref "R9") (pin "2") (pinfunction "2_2") (pintype "passive"))
    )
    (net (code "35") (name "/X1") (class "Default")
      (node (ref "R62") (pin "1") (pinfunction "1_1") (pintype "passive"))
      (node (ref "S2") (pin "1") (pintype "passive"))
    )
    (net (code "36") (name "/XS_R") (class "Default")
      (node (ref "P8") (pin "2") (pinfunction "2_2") (pintype "passive"))
      (node (ref "U1") (pin "25") (pinfunction "UART_L0_RXD_25") (pintype "passive"))
    )
    (net (code "37") (name "/XS_RST") (class "Default")
      (node (ref "R33") (pin "1") (pinfunction "1_1") (pintype "passive"))
    )
    (net (code "38") (name "/XS_T") (class "Default")
      (node (ref "P8") (pin "1") (pinfunction "1_1") (pintype "passive"))
      (node (ref "U1") (pin "24") (pinfunction "UART_L0_TXD_24") (pintype "passive"))
    )
    (net (code "39") (name "3.3V") (class "Default")
      (node (ref "C4") (pin "1") (pinfunction "1_1") (pintype "passive"))
      (node (ref "C5") (pin "1") (pinfunction "1_1") (pintype "passive"))
      (node (ref "C54") (pin "1") (pinfunction "1_1") (pintype "passive"))
      (node (ref "C55") (pin "1") (pinfunction "1_1") (pintype "passive"))
      (node (ref "Q1") (pin "2") (pinfunction "S_2") (pintype "passive"))
      (node (ref "Q2") (pin "2") (pinfunction "E_2") (pintype "passive"))
      (node (ref "R20") (pin "1") (pinfunction "1_1") (pintype "passive"))
      (node (ref "R62") (pin "2") (pinfunction "2_2") (pintype "passive"))
      (node (ref "TP4") (pin "1") (pinfunction "1_1") (pintype "passive"))
      (node (ref "U3") (pin "3") (pinfunction "Vout_3") (pintype "passive"))
    )
    (net (code "40") (name "3.6V") (class "Default")
      (node (ref "C10") (pin "1") (pinfunction "1_1") (pintype "passive"))
      (node (ref "C3") (pin "1") (pinfunction "1_1") (pintype "passive"))
      (node (ref "C59") (pin "1") (pinfunction "1_1") (pintype "passive"))
      (node (ref "D3") (pin "2") (pinfunction "2_2") (pintype "passive"))
      (node (ref "D4") (pin "3") (pinfunction "C_3") (pintype "passive"))
      (node (ref "TP3") (pin "1") (pinfunction "1_1") (pintype "passive"))
      (node (ref "U3") (pin "2") (pinfunction "Vin_2") (pintype "passive"))
    )
    (net (code "41") (name "5V") (class "Default")
      (node (ref "C23") (pin "2") (pinfunction "2_2") (pintype "passive"))
      (node (ref "C6") (pin "1") (pinfunction "1_1") (pintype "passive"))
      (node (ref "D11") (pin "1") (pinfunction "1_1") (pintype "passive"))
      (node (ref "D3") (pin "1") (pinfunction "1_1") (pintype "passive"))
      (node (ref "R30") (pin "2") (pinfunction "2_2") (pintype "passive"))
      (node (ref "TP2") (pin "1") (pinfunction "1_1") (pintype "passive"))
      (node (ref "U2") (pin "3") (pinfunction "Vout_3") (pintype "passive"))
      (node (ref "U5") (pin "1") (pinfunction "VM_1") (pintype "passive"))
    )
    (net (code "42") (name "GND") (class "Default")
      (node (ref "C1") (pin "2") (pinfunction "2_2") (pintype "passive"))
      (node (ref "C10") (pin "2") (pinfunction "2_2") (pintype "passive"))
      (node (ref "C11") (pin "2") (pinfunction "2_2") (pintype "passive"))
      (node (ref "C12") (pin "2") (pinfunction "2_2") (pintype "passive"))
      (node (ref "C13") (pin "2") (pinfunction "2_2") (pintype "passive"))
      (node (ref "C14") (pin "2") (pinfunction "2_2") (pintype "passive"))
      (node (ref "C15") (pin "2") (pinfunction "2_2") (pintype "passive"))
      (node (ref "C16") (pin "2") (pinfunction "2_2") (pintype "passive"))
      (node (ref "C17") (pin "2") (pinfunction "2_2") (pintype "passive"))
      (node (ref "C18") (pin "2") (pinfunction "2_2") (pintype "passive"))
      (node (ref "C19") (pin "2") (pinfunction "2_2") (pintype "passive"))
      (node (ref "C2") (pin "2") (pinfunction "2_2") (pintype "passive"))
      (node (ref "C20") (pin "2") (pinfunction "2_2") (pintype "passive"))
      (node (ref "C21") (pin "2") (pinfunction "2_2") (pintype "passive"))
      (node (ref "C22") (pin "1") (pinfunction "1_1") (pintype "passive"))
      (node (ref "C23") (pin "1") (pinfunction "1_1") (pintype "passive"))
      (node (ref "C3") (pin "2") (pinfunction "2_2") (pintype "passive"))
      (node (ref "C34") (pin "2") (pinfunction "2_2") (pintype "passive"))
      (node (ref "C37") (pin "2") (pinfunction "2_2") (pintype "passive"))
      (node (ref "C4") (pin "2") (pinfunction "2_2") (pintype "passive"))
      (node (ref "C40") (pin "2") (pinfunction "2_2") (pintype "passive"))
      (node (ref "C44") (pin "2") (pinfunction "2_2") (pintype "passive"))
      (node (ref "C47") (pin "2") (pinfunction "2_2") (pintype "passive"))
      (node (ref "C5") (pin "2") (pinfunction "2_2") (pintype "passive"))
      (node (ref "C51") (pin "1") (pinfunction "1_1") (pintype "passive"))
      (node (ref "C54") (pin "2") (pinfunction "2_2") (pintype "passive"))
      (node (ref "C55") (pin "2") (pinfunction "2_2") (pintype "passive"))
      (node (ref "C57") (pin "2") (pinfunction "2_2") (pintype "passive"))
      (node (ref "C59") (pin "2") (pinfunction "2_2") (pintype "passive"))
      (node (ref "C7") (pin "2") (pinfunction "2_2") (pintype "passive"))
      (node (ref "C9") (pin "2") (pinfunction "2_2") (pintype "passive"))
      (node (ref "J4") (pin "1") (pinfunction "1_1") (pintype "passive"))
      (node (ref "P1") (pin "1") (pinfunction "1_1") (pintype "passive"))
      (node (ref "P2") (pin "1") (pinfunction "1_1") (pintype "passive"))
      (node (ref "P8") (pin "3") (pinfunction "3_3") (pintype "passive"))
      (node (ref "Q14") (pin "2") (pinfunction "E_2") (pintype "passive"))
      (node (ref "Q15") (pin "2") (pinfunction "E_2") (pintype "passive"))
      (node (ref "Q3") (pin "2") (pinfunction "E_2") (pintype "passive"))
      (node (ref "R48") (pin "2") (pinfunction "2_2") (pintype "passive"))
      (node (ref "R56") (pin "2") (pinfunction "2_2") (pintype "passive"))
      (node (ref "R58") (pin "2") (pinfunction "2_2") (pintype "passive"))
      (node (ref "S2") (pin "2") (pintype "passive"))
      (node (ref "SIM1") (pin "1") (pinfunction "VSS_1") (pintype "passive"))
      (node (ref "TP5") (pin "1") (pinfunction "1_1") (pintype "passive"))
      (node (ref "TP6") (pin "1") (pinfunction "1_1") (pintype "passive"))
      (node (ref "U1") (pin "11") (pinfunction "GND_11") (pintype "passive"))
      (node (ref "U1") (pin "2") (pinfunction "GND_2") (pintype "passive"))
      (node (ref "U1") (pin "26") (pinfunction "GND_26") (pintype "passive"))
      (node (ref "U1") (pin "29") (pinfunction "GND_29") (pintype "passive"))
      (node (ref "U1") (pin "30") (pinfunction "GND_30") (pintype "passive"))
      (node (ref "U1") (pin "31") (pinfunction "GND_31") (pintype "passive"))
      (node (ref "U1") (pin "33") (pinfunction "GND_TP_33") (pintype "passive"))
      (node (ref "U1") (pin "38") (pinfunction "GND_38") (pintype "passive"))
      (node (ref "U2") (pin "1") (pinfunction "GND_1") (pintype "passive"))
      (node (ref "U21") (pin "21") (pinfunction "IO_1833_SEL_21") (pintype "passive"))
      (node (ref "U21") (pin "23") (pinfunction "GND_23") (pintype "passive"))
      (node (ref "U21") (pin "24") (pinfunction "GND_24") (pintype "passive"))
      (node (ref "U21") (pin "25") (pinfunction "GND_25") (pintype "passive"))
      (node (ref "U21") (pin "26") (pinfunction "GND_26") (pintype "passive"))
      (node (ref "U21") (pin "4") (pinfunction "GND_4") (pintype "passive"))
      (node (ref "U21") (pin "5") (pinfunction "GND_5") (pintype "passive"))
      (node (ref "U3") (pin "1") (pinfunction "GND_1") (pintype "passive"))
      (node (ref "U4") (pin "1") (pinfunction "GND_1") (pintype "passive"))
      (node (ref "U5") (pin "4") (pinfunction "GND_4") (pintype "passive"))
      (node (ref "U5") (pin "9") (pinfunction "Pad_9") (pintype "passive"))
      (node (ref "U8") (pin "1") (pinfunction "GND_1") (pintype "passive"))
      (node (ref "W1") (pin "2") (pinfunction "GND_2") (pintype "passive"))
    )
    (net (code "43") (name "GPRS_3.6V") (class "Default")
      (node (ref "C16") (pin "1") (pinfunction "1_1") (pintype "passive"))
      (node (ref "C17") (pin "1") (pinfunction "1_1") (pintype "passive"))
      (node (ref "C18") (pin "1") (pinfunction "1_1") (pintype "passive"))
      (node (ref "C37") (pin "1") (pinfunction "1_1") (pintype "passive"))
      (node (ref "C9") (pin "1") (pinfunction "1_1") (pintype "passive"))
      (node (ref "Q4") (pin "3") (pinfunction "D_3") (pintype "passive"))
      (node (ref "U21") (pin "6") (pinfunction "VBAT_6") (pintype "passive"))
      (node (ref "U21") (pin "7") (pinfunction "VBAT_7") (pintype "passive"))
    )
    (net (code "44") (name "Net-(C44-Pad1)") (class "Default")
      (node (ref "C44") (pin "1") (pinfunction "1_1") (pintype "passive"))
      (node (ref "C6") (pin "2") (pinfunction "2_2") (pintype "passive"))
    )
    (net (code "45") (name "Net-(D4-A-Pad1)") (class "Default")
      (node (ref "D4") (pin "1") (pinfunction "A_1") (pintype "passive"))
      (node (ref "D4") (pin "2") (pinfunction "A_2") (pintype "passive"))
      (node (ref "P2") (pin "2") (pinfunction "2_2") (pintype "passive"))
      (node (ref "TP7") (pin "1") (pinfunction "1_1") (pintype "passive"))
    )
    (net (code "46") (name "Net-(Q1-G)") (class "Default")
      (node (ref "Q1") (pin "1") (pinfunction "G_1") (pintype "passive"))
      (node (ref "R20") (pin "2") (pinfunction "2_2") (pintype "passive"))
      (node (ref "R32") (pin "2") (pinfunction "2_2") (pintype "passive"))
    )
    (net (code "47") (name "Net-(Q2-B)") (class "Default")
      (node (ref "Q2") (pin "1") (pinfunction "B_1") (pintype "passive"))
      (node (ref "R44") (pin "2") (pinfunction "2_2") (pintype "passive"))
    )
    (net (code "48") (name "Net-(Q2-C)") (class "Default")
      (node (ref "C34") (pin "1") (pinfunction "1_1") (pintype "passive"))
      (node (ref "Q2") (pin "3") (pinfunction "C_3") (pintype "passive"))
      (node (ref "R45") (pin "1") (pinfunction "1_1") (pintype "passive"))
      (node (ref "U8") (pin "8") (pinfunction "VCC_8") (pintype "passive"))
    )
    (net (code "49") (name "Net-(Q3-B)") (class "Default")
      (node (ref "Q3") (pin "1") (pinfunction "B_1") (pintype "passive"))
      (node (ref "R33") (pin "2") (pinfunction "2_2") (pintype "passive"))
      (node (ref "R48") (pin "1") (pinfunction "1_1") (pintype "passive"))
    )
    (net (code "50") (name "Net-(Q3-C)") (class "Default")
      (node (ref "Q3") (pin "3") (pinfunction "C_3") (pintype "passive"))
      (node (ref "U1") (pin "12") (pinfunction "nRESET_12") (pintype "passive"))
    )
    (net (code "51") (name "Net-(Q4-G)") (class "Default")
      (node (ref "Q4") (pin "1") (pinfunction "G_1") (pintype "passive"))
      (node (ref "R16") (pin "1") (pinfunction "1_1") (pintype "passive"))
      (node (ref "R18") (pin "2") (pinfunction "2_2") (pintype "passive"))
    )
    (net (code "52") (name "Net-(Q4-S)") (class "Default")
      (node (ref "C40") (pin "1") (pinfunction "1_1") (pintype "passive"))
      (node (ref "Q4") (pin "2") (pinfunction "S_2") (pintype "passive"))
      (node (ref "R16") (pin "2") (pinfunction "2_2") (pintype "passive"))
      (node (ref "R50") (pin "2") (pinfunction "2_2") (pintype "passive"))
      (node (ref "U4") (pin "3") (pinfunction "Vout_3") (pintype "passive"))
    )
    (net (code "53") (name "Net-(Q13-B)") (class "Default")
      (node (ref "Q13") (pin "1") (pinfunction "B_1") (pintype "passive"))
      (node (ref "R55") (pin "2") (pinfunction "2_2") (pintype "passive"))
    )
    (net (code "54") (name "Net-(Q13-C)") (class "Default")
      (node (ref "Q13") (pin "3") (pinfunction "C_3") (pintype "passive"))
      (node (ref "R9") (pin "1") (pinfunction "1_1") (pintype "passive"))
    )
    (net (code "55") (name "Net-(Q14-B)") (class "Default")
      (node (ref "Q14") (pin "1") (pinfunction "B_1") (pintype "passive"))
      (node (ref "R14") (pin "2") (pinfunction "2_2") (pintype "passive"))
    )
    (net (code "56") (name "Net-(Q14-C)") (class "Default")
      (node (ref "Q14") (pin "3") (pinfunction "C_3") (pintype "passive"))
      (node (ref "R10") (pin "1") (pinfunction "1_1") (pintype "passive"))
      (node (ref "R55") (pin "1") (pinfunction "1_1") (pintype "passive"))
    )
    (net (code "57") (name "Net-(Q15-B)") (class "Default")
      (node (ref "Q15") (pin "1") (pinfunction "B_1") (pintype "passive"))
      (node (ref "R57") (pin "2") (pinfunction "2_2") (pintype "passive"))
      (node (ref "R58") (pin "1") (pinfunction "1_1") (pintype "passive"))
    )
    (net (code "58") (name "Net-(U1A-BUSY_IND)") (class "Default")
      (node (ref "R13") (pin "2") (pinfunction "2_2") (pintype "passive"))
      (node (ref "U1") (pin "23") (pinfunction "BUSY_IND_23") (pintype "passive"))
    )
    (net (code "59") (name "Net-(U1A-DOUT_IND)") (class "Default")
      (node (ref "R17") (pin "2") (pinfunction "2_2") (pintype "passive"))
      (node (ref "U1") (pin "22") (pinfunction "DOUT_IND_22") (pintype "passive"))
    )
    (net (code "60") (name "Net-(U1A-PWR_CTL)") (class "Default")
      (node (ref "R15") (pin "1") (pinfunction "1_1") (pintype "passive"))
      (node (ref "U1") (pin "6") (pinfunction "PWR_CTL_6") (pintype "passive"))
    )
    (net (code "61") (name "Net-(U1A-PWR_IND)") (class "Default")
      (node (ref "R19") (pin "2") (pinfunction "2_2") (pintype "passive"))
      (node (ref "U1") (pin "21") (pinfunction "PWR_IND_21") (pintype "passive"))
    )
    (net (code "62") (name "Net-(U21-ANT)") (class "Default")
      (node (ref "C1") (pin "1") (pinfunction "1_1") (pintype "passive"))
      (node (ref "R2") (pin "2") (pinfunction "2_2") (pintype "passive"))
      (node (ref "U21") (pin "22") (pinfunction "ANT_22") (pintype "passive"))
    )
    (net (code "63") (name "Net-(W1-ANT)") (class "Default")
      (node (ref "C2") (pin "1") (pinfunction "1_1") (pintype "passive"))
      (node (ref "R2") (pin "1") (pinfunction "1_1") (pintype "passive"))
      (node (ref "W1") (pin "1") (pinfunction "ANT_1") (pintype "passive"))
    )
    (net (code "64") (name "USIM_VDD") (class "Default")
      (node (ref "C11") (pin "1") (pinfunction "1_1") (pintype "passive"))
      (node (ref "C12") (pin "1") (pinfunction "1_1") (pintype "passive"))
      (node (ref "R12") (pin "2") (pinfunction "2_2") (pintype "passive"))
      (node (ref "SIM1") (pin "8") (pinfunction "VDD_8") (pintype "passive"))
      (node (ref "U21") (pin "18") (pinfunction "VO_LDOSIM_18") (pintype "passive"))
    )
    (net (code "65") (name "VDD_XS") (class "Default")
      (node (ref "C13") (pin "1") (pinfunction "1_1") (pintype "passive"))
      (node (ref "C15") (pin "1") (pinfunction "1_1") (pintype "passive"))
      (node (ref "Q1") (pin "3") (pinfunction "D_3") (pintype "passive"))
      (node (ref "R28") (pin "1") (pinfunction "1_1") (pintype "passive"))
      (node (ref "U1") (pin "10") (pinfunction "VBAT_10") (pintype "passive"))
    )
    (net (code "66") (name "VIN_N") (class "Default")
      (node (ref "C14") (pin "1") (pinfunction "1_1") (pintype "passive"))
      (node (ref "C47") (pin "1") (pinfunction "1_1") (pintype "passive"))
      (node (ref "C7") (pin "1") (pinfunction "1_1") (pintype "passive"))
      (node (ref "D11") (pin "2") (pinfunction "2_2") (pintype "passive"))
      (node (ref "D2") (pin "2") (pinfunction "2_2") (pintype "passive"))
      (node (ref "R30") (pin "1") (pinfunction "1_1") (pintype "passive"))
      (node (ref "R50") (pin "1") (pinfunction "1_1") (pintype "passive"))
      (node (ref "U2") (pin "2") (pinfunction "Vin_2") (pintype "passive"))
      (node (ref "U4") (pin "2") (pinfunction "Vin_2") (pintype "passive"))
    )
    (net (code "67") (name "Vin") (class "Default")
      (node (ref "D2") (pin "1") (pinfunction "1_1") (pintype "passive"))
      (node (ref "P1") (pin "2") (pinfunction "2_2") (pintype "passive"))
      (node (ref "Q13") (pin "2") (pinfunction "E_2") (pintype "passive"))
      (node (ref "R10") (pin "2") (pinfunction "2_2") (pintype "passive"))
      (node (ref "TP1") (pin "1") (pinfunction "1_1") (pintype "passive"))
    )
    (net (code "68") (name "unconnected-(SIM1-NC-Pad4)") (class "Default")
      (node (ref "SIM1") (pin "4") (pinfunction "NC_4") (pintype "passive"))
    )
    (net (code "69") (name "unconnected-(SIM1-NC-Pad5)") (class "Default")
      (node (ref "SIM1") (pin "5") (pinfunction "NC_5") (pintype "passive"))
    )
    (net (code "70") (name "unconnected-(U1A-ANT-Pad27)") (class "Default")
      (node (ref "U1") (pin "27") (pinfunction "ANT_27") (pintype "passive"))
    )
    (net (code "71") (name "unconnected-(U1A-MIC_LDO-Pad1)") (class "Default")
      (node (ref "U1") (pin "1") (pinfunction "MIC_LDO_1") (pintype "passive"))
    )
    (net (code "72") (name "unconnected-(U1A-REV-Pad3)") (class "Default")
      (node (ref "U1") (pin "3") (pinfunction "REV_3") (pintype "passive"))
    )
    (net (code "73") (name "unconnected-(U1A-REV-Pad4)") (class "Default")
      (node (ref "U1") (pin "4") (pinfunction "REV_4") (pintype "passive"))
    )
    (net (code "74") (name "unconnected-(U1A-REV-Pad5)") (class "Default")
      (node (ref "U1") (pin "5") (pinfunction "REV_5") (pintype "passive"))
    )
    (net (code "75") (name "unconnected-(U1A-REV-Pad19)") (class "Default")
      (node (ref "U1") (pin "19") (pinfunction "REV_19") (pintype "passive"))
    )
    (net (code "76") (name "unconnected-(U1A-REV-Pad20)") (class "Default")
      (node (ref "U1") (pin "20") (pinfunction "REV_20") (pintype "passive"))
    )
    (net (code "77") (name "unconnected-(U1A-SWCLK-Pad13)") (class "Default")
      (node (ref "U1") (pin "13") (pinfunction "SWCLK_13") (pintype "passive"))
    )
    (net (code "78") (name "unconnected-(U1A-SWDIO-Pad14)") (class "Default")
      (node (ref "U1") (pin "14") (pinfunction "SWDIO_14") (pintype "passive"))
    )
    (net (code "79") (name "unconnected-(U1A-TEST_IO-Pad9)") (class "Default")
      (node (ref "U1") (pin "9") (pinfunction "TEST_IO_9") (pintype "passive"))
    )
    (net (code "80") (name "unconnected-(U1A-UART_L1_RXD-Pad8)") (class "Default")
      (node (ref "U1") (pin "8") (pinfunction "UART_L1_RXD_8") (pintype "passive"))
    )
    (net (code "81") (name "unconnected-(U1A-UART_L1_TXD-Pad7)") (class "Default")
      (node (ref "U1") (pin "7") (pinfunction "UART_L1_TXD_7") (pintype "passive"))
    )
    (net (code "82") (name "unconnected-(U1A-USB_DN-Pad16)") (class "Default")
      (node (ref "U1") (pin "16") (pinfunction "USB_DN_16") (pintype "passive"))
    )
    (net (code "83") (name "unconnected-(U1A-USB_DP-Pad15)") (class "Default")
      (node (ref "U1") (pin "15") (pinfunction "USB_DP_15") (pintype "passive"))
    )
    (net (code "84") (name "unconnected-(U1B-ANT_TP-Pad32)") (class "Default")
      (node (ref "U1") (pin "32") (pinfunction "ANT_TP_32") (pintype "passive"))
    )
    (net (code "85") (name "unconnected-(U1B-NC-Pad28)") (class "Default")
      (node (ref "U1") (pin "28") (pinfunction "NC_28") (pintype "passive"))
    )
    (net (code "86") (name "unconnected-(U1B-NC-Pad44)") (class "Default")
      (node (ref "U1") (pin "44") (pinfunction "NC_44") (pintype "passive"))
    )
    (net (code "87") (name "unconnected-(U1B-NC-Pad45)") (class "Default")
      (node (ref "U1") (pin "45") (pinfunction "NC_45") (pintype "passive"))
    )
    (net (code "88") (name "unconnected-(U1B-REV-Pad34)") (class "Default")
      (node (ref "U1") (pin "34") (pinfunction "REV_34") (pintype "passive"))
    )
    (net (code "89") (name "unconnected-(U1B-REV-Pad35)") (class "Default")
      (node (ref "U1") (pin "35") (pinfunction "REV_35") (pintype "passive"))
    )
    (net (code "90") (name "unconnected-(U1B-REV-Pad36)") (class "Default")
      (node (ref "U1") (pin "36") (pinfunction "REV_36") (pintype "passive"))
    )
    (net (code "91") (name "unconnected-(U1B-REV-Pad37)") (class "Default")
      (node (ref "U1") (pin "37") (pinfunction "REV_37") (pintype "passive"))
    )
    (net (code "92") (name "unconnected-(U1B-REV-Pad39)") (class "Default")
      (node (ref "U1") (pin "39") (pinfunction "REV_39") (pintype "passive"))
    )
    (net (code "93") (name "unconnected-(U1B-REV-Pad40)") (class "Default")
      (node (ref "U1") (pin "40") (pinfunction "REV_40") (pintype "passive"))
    )
    (net (code "94") (name "unconnected-(U1B-REV-Pad41)") (class "Default")
      (node (ref "U1") (pin "41") (pinfunction "REV_41") (pintype "passive"))
    )
    (net (code "95") (name "unconnected-(U1B-REV-Pad43)") (class "Default")
      (node (ref "U1") (pin "43") (pinfunction "REV_43") (pintype "passive"))
    )
    (net (code "96") (name "unconnected-(U1B-REV-Pad46)") (class "Default")
      (node (ref "U1") (pin "46") (pinfunction "REV_46") (pintype "passive"))
    )
    (net (code "97") (name "unconnected-(U1B-REV-Pad47)") (class "Default")
      (node (ref "U1") (pin "47") (pinfunction "REV_47") (pintype "passive"))
    )
    (net (code "98") (name "unconnected-(U1B-TEST_IO-Pad42)") (class "Default")
      (node (ref "U1") (pin "42") (pinfunction "TEST_IO_42") (pintype "passive"))
    )
    (net (code "99") (name "unconnected-(U8-NC-Pad2)") (class "Default")
      (node (ref "U8") (pin "2") (pinfunction "NC_2") (pintype "passive"))
    )
    (net (code "100") (name "unconnected-(U8-NC-Pad4)") (class "Default")
      (node (ref "U8") (pin "4") (pinfunction "NC_4") (pintype "passive"))
    )
    (net (code "101") (name "unconnected-(U8-NC-Pad5)") (class "Default")
      (node (ref "U8") (pin "5") (pinfunction "NC_5") (pintype "passive"))
    )
    (net (code "102") (name "unconnected-(U21-ADC0-Pad14)") (class "Default")
      (node (ref "U21") (pin "14") (pinfunction "ADC0_14") (pintype "passive+no_connect"))
    )
    (net (code "103") (name "unconnected-(U21-GPIO1-Pad27)") (class "Default")
      (node (ref "U21") (pin "27") (pinfunction "GPIO1_27") (pintype "passive+no_connect"))
    )
    (net (code "104") (name "unconnected-(U21-GPIO4-Pad13)") (class "Default")
      (node (ref "U21") (pin "13") (pinfunction "GPIO4_13") (pintype "passive+no_connect"))
    )
    (net (code "105") (name "unconnected-(U21-GPIO5-Pad12)") (class "Default")
      (node (ref "U21") (pin "12") (pinfunction "GPIO5_12") (pintype "passive+no_connect"))
    )
    (net (code "106") (name "unconnected-(U21-GPIO6-Pad11)") (class "Default")
      (node (ref "U21") (pin "11") (pinfunction "GPIO6_11") (pintype "passive+no_connect"))
    )
    (net (code "107") (name "unconnected-(U21-GPIO12-Pad1)") (class "Default")
      (node (ref "U21") (pin "1") (pinfunction "GPIO12_1") (pintype "passive+no_connect"))
    )
    (net (code "108") (name "unconnected-(U21-GPIO13-Pad28)") (class "Default")
      (node (ref "U21") (pin "28") (pinfunction "GPIO13_28") (pintype "passive+no_connect"))
    )
    (net (code "109") (name "unconnected-(U21-WAKEUP-Pad19)") (class "Default")
      (node (ref "U21") (pin "19") (pinfunction "WAKEUP_19") (pintype "passive"))
    )
  )
)
